# Battery_eFuse.net
KiCad netlist of a schematic drawn in Altium Designer
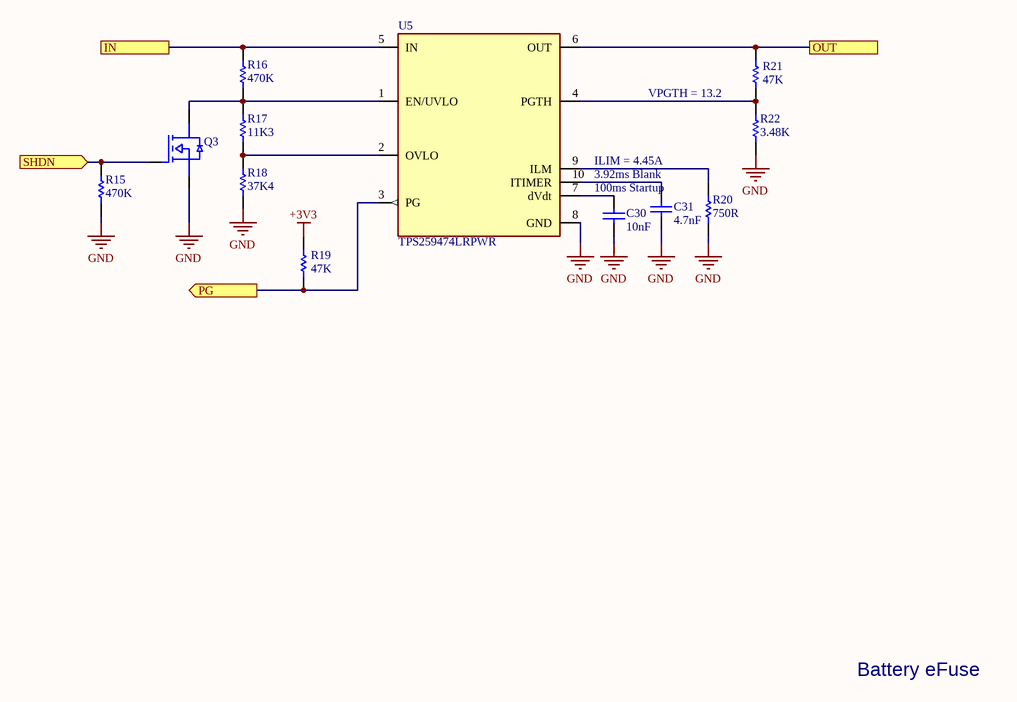
[diagram p0: Battery_eFuse.SchDoc]

(export (version "E")
  (design (tool "Eeschema 10.0.6"))
  (components
    (comp (ref "C30")
      (value "CL10B103KB8NNNC")
      (footprint "CAPC0603X060")
      (description "10nF ±10% 50V Ceramic Capacitor X7R 0603 (1608 Metric)")
      (fields
        (field (name "DISTRIBUTOR PART NUMBER") "1276-1009-1-ND")
        (field (name "TOLERANCE") "10%")
        (field (name "CAPACITANCE") "10nF")
      )
      (libsource (lib "Ahristi_Library") (part "CL10B103KB8NNNC"))
    )
    (comp (ref "C31")
      (value "C0603C472K4RECAUTO")
      (footprint "CAPC0603X040")
      (description "4.7nF ±10% 16V Ceramic Capacitor X7R 0603 (1608 Metric)")
      (fields
        (field (name "TOLERANCE") "10%")
        (field (name "DISTRIBUTOR PART NUMBER") "399-17879-1-ND")
        (field (name "CAPACITANCE") "4.7nF")
      )
      (libsource (lib "Ahristi_Library") (part "C0603C472K4RECAUTO"))
    )
    (comp (ref "Q3")
      (value "T2N7002AK,LM")
      (footprint "SOT23-3 MOSFET")
      (description "N-Channel 60 V 200mA (Ta) 320mW (Ta) Surface Mount SOT-23-3")
      (fields (field (name "DISTRIBUTOR PART NUMBER") "T2N7002AKLMCT-ND"))
      (libsource (lib "Ahristi_Library") (part "T2N7002AK,LM"))
    )
    (comp (ref "R15")
      (value "RMCF0603FT470K")
      (footprint "RESC0603")
      (description "470 kOhms ±1% 0.1W, 1/10W Chip Resistor 0603 (1608 Metric) Automotive AEC-Q200 Thick Film")
      (fields
        (field (name "TOLERANCE") "1%")
        (field (name "DISTRIBUTOR PART NUMBER") "RMCF0603FT470KCT-ND")
        (field (name "RESISTANCE") "470K")
      )
      (libsource (lib "Ahristi_Library") (part "RMCF0603FT470K"))
    )
    (comp (ref "R16")
      (value "RMCF0603FT470K")
      (footprint "RESC0603")
      (description "470 kOhms ±1% 0.1W, 1/10W Chip Resistor 0603 (1608 Metric) Automotive AEC-Q200 Thick Film")
      (fields
        (field (name "TOLERANCE") "1%")
        (field (name "DISTRIBUTOR PART NUMBER") "RMCF0603FT470KCT-ND")
        (field (name "RESISTANCE") "470K")
      )
      (libsource (lib "Ahristi_Library") (part "RMCF0603FT470K"))
    )
    (comp (ref "R17")
      (value "RMCF0603FT11K3")
      (footprint "RESC0603")
      (description "11.3 kOhms ±1% 0.1W, 1/10W Chip Resistor 0603 (1608 Metric) Automotive AEC-Q200 Thick Film")
      (fields
        (field (name "DISTRIBUTOR PART NUMBER") "RMCF0603FT11K3CT-ND")
        (field (name "TOLERANCE") "1%")
        (field (name "RESISTANCE") "11K3")
      )
      (libsource (lib "Ahristi_Library") (part "RMCF0603FT11K3"))
    )
    (comp (ref "R18")
      (value "RMCF0603FT37K4")
      (footprint "RESC0603")
      (description "37.4 kOhms ±1% 0.1W, 1/10W Chip Resistor 0603 (1608 Metric) Automotive AEC-Q200 Thick Film")
      (fields
        (field (name "TOLERANCE") "1%")
        (field (name "DISTRIBUTOR PART NUMBER") "RMCF0603FT37K4CT-ND")
        (field (name "RESISTANCE") "37K4")
      )
      (libsource (lib "Ahristi_Library") (part "RMCF0603FT37K4"))
    )
    (comp (ref "R19")
      (value "RMCF0603FT47K0")
      (footprint "RESC0603")
      (description "47 kOhms ±1% 0.1W, 1/10W Chip Resistor 0603 (1608 Metric) Automotive AEC-Q200 Thick Film")
      (fields
        (field (name "TOLERANCE") "1%")
        (field (name "DISTRIBUTOR PART NUMBER") "RMCF0603FT47K0CT-ND")
        (field (name "RESISTANCE") "47K")
      )
      (libsource (lib "Ahristi_Library") (part "RMCF0603FT47K0"))
    )
    (comp (ref "R20")
      (value "RMCF0603FT750R")
      (footprint "RESC0603")
      (description "750 Ohms ±1% 0.1W, 1/10W Chip Resistor 0603 (1608 Metric) Automotive AEC-Q200 Thick Film")
      (fields
        (field (name "TOLERANCE") "1%")
        (field (name "DISTRIBUTOR PART NUMBER") "RMCF0603FT750RCT-ND")
        (field (name "RESISTANCE") "750R")
      )
      (libsource (lib "Ahristi_Library") (part "RMCF0603FT750R"))
    )
    (comp (ref "R21")
      (value "RMCF0603FT47K0")
      (footprint "RESC0603")
      (description "47 kOhms ±1% 0.1W, 1/10W Chip Resistor 0603 (1608 Metric) Automotive AEC-Q200 Thick Film")
      (fields
        (field (name "TOLERANCE") "1%")
        (field (name "DISTRIBUTOR PART NUMBER") "RMCF0603FT47K0CT-ND")
        (field (name "RESISTANCE") "47K")
      )
      (libsource (lib "Ahristi_Library") (part "RMCF0603FT47K0"))
    )
    (comp (ref "R22")
      (value "RMCF0603FT3K48")
      (footprint "RESC0603")
      (description "3.48 kOhms ±1% 0.1W, 1/10W Chip Resistor 0603 (1608 Metric) Automotive AEC-Q200 Thick Film")
      (fields
        (field (name "TOLERANCE") "1%")
        (field (name "DISTRIBUTOR PART NUMBER") "RMCF0603FT3K48CT-ND")
        (field (name "RESISTANCE") "3.48K")
      )
      (libsource (lib "Ahristi_Library") (part "RMCF0603FT3K48"))
    )
    (comp (ref "U5")
      (value "TPS259474LRPWR")
      (footprint "VFQFN-10")
      (description "eFuse 5.5A, 2.7V~23V, 28mOhm, Reverse Current Blocking with Input Reverse Polarity Protection")
      (fields (field (name "DISTRIBUTOR PART NUMBER") "296-TPS259474LRPWRCT-ND"))
      (libsource (lib "Ahristi_Library") (part "TPS259474LRPWR"))
    )
  )
  (nets
    (net (code "1") (name "+3V3") (class "Default")
      (node (ref "R19") (pin "2") (pinfunction "2_2") (pintype "passive"))
    )
    (net (code "2") (name "/IN") (class "Default")
      (node (ref "R16") (pin "2") (pinfunction "2_2") (pintype "passive"))
      (node (ref "U5") (pin "5") (pinfunction "IN_5") (pintype "passive"))
    )
    (net (code "3") (name "/OUT") (class "Default")
      (node (ref "R21") (pin "2") (pinfunction "2_2") (pintype "passive"))
      (node (ref "U5") (pin "6") (pinfunction "OUT_6") (pintype "passive"))
    )
    (net (code "4") (name "/PG") (class "Default")
      (node (ref "R19") (pin "1") (pinfunction "1_1") (pintype "passive"))
      (node (ref "U5") (pin "3") (pinfunction "PG_3") (pintype "output"))
    )
    (net (code "5") (name "/SHDN") (class "Default")
      (node (ref "Q3") (pin "G") (pinfunction "G_G") (pintype "passive"))
      (node (ref "R15") (pin "2") (pinfunction "2_2") (pintype "passive"))
    )
    (net (code "6") (name "GND") (class "Default")
      (node (ref "C30") (pin "1") (pinfunction "1_1") (pintype "passive"))
      (node (ref "C31") (pin "1") (pinfunction "1_1") (pintype "passive"))
      (node (ref "Q3") (pin "S") (pinfunction "S_S") (pintype "passive"))
      (node (ref "R15") (pin "1") (pinfunction "1_1") (pintype "passive"))
      (node (ref "R18") (pin "1") (pinfunction "1_1") (pintype "passive"))
      (node (ref "R20") (pin "1") (pinfunction "1_1") (pintype "passive"))
      (node (ref "R22") (pin "1") (pinfunction "1_1") (pintype "passive"))
      (node (ref "U5") (pin "8") (pinfunction "GND_8") (pintype "passive"))
    )
    (net (code "7") (name "Net-(U5-EN{slash}UVLO)") (class "Default")
      (node (ref "Q3") (pin "D") (pinfunction "D_D") (pintype "passive"))
      (node (ref "R16") (pin "1") (pinfunction "1_1") (pintype "passive"))
      (node (ref "R17") (pin "2") (pinfunction "2_2") (pintype "passive"))
      (node (ref "U5") (pin "1") (pinfunction "EN/UVLO_1") (pintype "passive"))
    )
    (net (code "8") (name "Net-(U5-ILM)") (class "Default")
      (node (ref "R20") (pin "2") (pinfunction "2_2") (pintype "passive"))
      (node (ref "U5") (pin "9") (pinfunction "ILM_9") (pintype "passive"))
    )
    (net (code "9") (name "Net-(U5-ITIMER)") (class "Default")
      (node (ref "C31") (pin "2") (pinfunction "2_2") (pintype "passive"))
      (node (ref "U5") (pin "10") (pinfunction "ITIMER_10") (pintype "passive"))
    )
    (net (code "10") (name "Net-(U5-OVLO)") (class "Default")
      (node (ref "R17") (pin "1") (pinfunction "1_1") (pintype "passive"))
      (node (ref "R18") (pin "2") (pinfunction "2_2") (pintype "passive"))
      (node (ref "U5") (pin "2") (pinfunction "OVLO_2") (pintype "passive"))
    )
    (net (code "11") (name "Net-(U5-PGTH)") (class "Default")
      (node (ref "R21") (pin "1") (pinfunction "1_1") (pintype "passive"))
      (node (ref "R22") (pin "2") (pinfunction "2_2") (pintype "passive"))
      (node (ref "U5") (pin "4") (pinfunction "PGTH_4") (pintype "passive"))
    )
    (net (code "12") (name "Net-(U5-dVdt)") (class "Default")
      (node (ref "C30") (pin "2") (pinfunction "2_2") (pintype "passive"))
      (node (ref "U5") (pin "7") (pinfunction "dVdt_7") (pintype "passive"))
    )
  )
)
